# ConnectorBoard.net
KiCad netlist of a schematic drawn in EAGLE
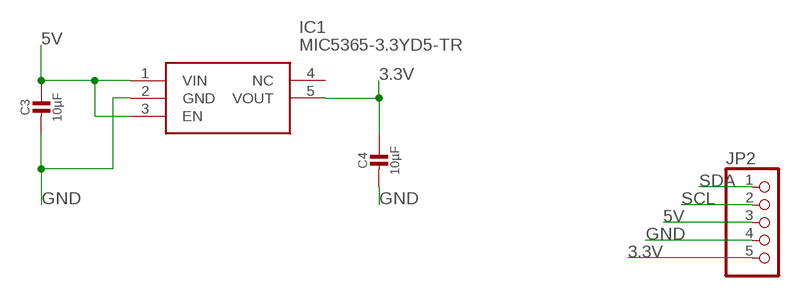
[diagram p0: schematic, sheet 1]

(export (version "E")
  (design (tool "Eeschema 10.0.6"))
  (components
    (comp (ref "C3")
      (value "10µF")
      (footprint "eagle-import:0805-NO")
      (libsource (lib "eagle-import") (part "CAP_CERAMIC0805-NOOUTLINE"))
    )
    (comp (ref "C4")
      (value "10µF")
      (footprint "eagle-import:0805-NO")
      (libsource (lib "eagle-import") (part "CAP_CERAMIC0805-NOOUTLINE"))
    )
    (comp (ref "IC1")
      (value "MIC5365-3.3YD5-TR")
      (footprint "eagle-import:SOT95P280X100-5N")
      (fields (field (name "MOUSER_PART_NUMBER") "998-MIC5365-3.3YD5TR"))
      (libsource (lib "eagle-import") (part "MIC5365-3.3YD5-TR"))
    )
    (comp (ref "JP2")
      (value "PINHD-1X55X2MM")
      (footprint "eagle-import:1_05X2MM")
      (libsource (lib "eagle-import") (part "PINHD-1X55X2MM"))
    )
  )
  (nets
    (net (code "1") (name "/3.3V") (class "Default")
      (node (ref "C4") (pin "1") (pinfunction "1_1") (pintype "passive"))
      (node (ref "IC1") (pin "5") (pinfunction "VOUT_5") (pintype "bidirectional"))
      (node (ref "JP2") (pin "5") (pinfunction "5_5") (pintype "passive"))
    )
    (net (code "2") (name "/5V") (class "Default")
      (node (ref "C3") (pin "1") (pinfunction "1_1") (pintype "passive"))
      (node (ref "IC1") (pin "1") (pinfunction "VIN_1") (pintype "bidirectional"))
      (node (ref "IC1") (pin "3") (pinfunction "EN_3") (pintype "bidirectional"))
      (node (ref "JP2") (pin "3") (pinfunction "3_3") (pintype "passive"))
    )
    (net (code "3") (name "/GND") (class "Default")
      (node (ref "C3") (pin "2") (pinfunction "2_2") (pintype "passive"))
      (node (ref "C4") (pin "2") (pinfunction "2_2") (pintype "passive"))
      (node (ref "IC1") (pin "2") (pinfunction "GND_2") (pintype "bidirectional"))
      (node (ref "JP2") (pin "4") (pinfunction "4_4") (pintype "passive"))
    )
    (net (code "4") (name "/SCL") (class "Default")
      (node (ref "JP2") (pin "2") (pinfunction "2_2") (pintype "passive"))
    )
    (net (code "5") (name "/SDA") (class "Default")
      (node (ref "JP2") (pin "1") (pinfunction "1_1") (pintype "passive"))
    )
    (net (code "6") (name "unconnected-(IC1-NC-Pad4)") (class "Default")
      (node (ref "IC1") (pin "4") (pinfunction "NC_4") (pintype "no_connect"))
    )
  )
)
